# ATMEGA328P_BASICO.net
KiCad netlist of a schematic drawn in EAGLE
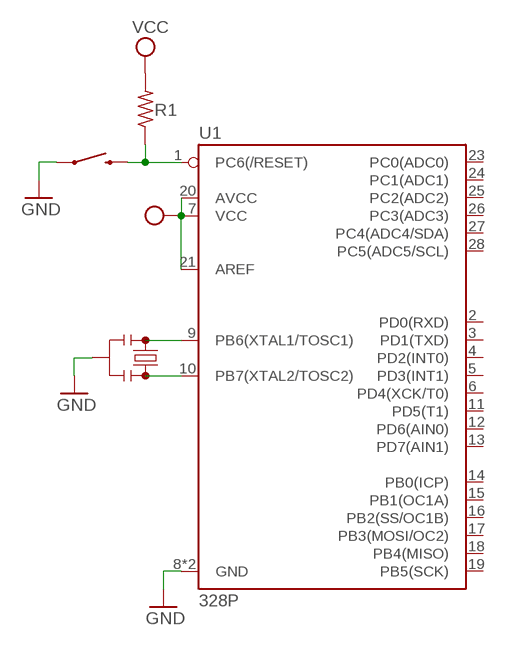
[diagram p0: schematic, sheet 1]

(export (version "E")
  (design (tool "Eeschema 10.0.6"))
  (components
    (comp (ref "R1")
      (value "R-US_0204/7")
      (footprint "eagle-import:0204_7")
      (libsource (lib "eagle-import") (part "R-US_0204/7"))
    )
    (comp (ref "S1")
      (value "MOMENTARY-SWITCH-SPST-SMD-6.2MM-TALL")
      (footprint "eagle-import:TACTILE_SWITCH_SMD_6.2MM_TALL")
      (libsource (lib "eagle-import") (part "MOMENTARY-SWITCH-SPST-SMD-6.2MM-TALL"))
    )
    (comp (ref "U1")
      (value "328P")
      (footprint "eagle-import:DIP28")
      (libsource (lib "eagle-import") (part "ATMEGA328P_PDIP"))
    )
    (comp (ref "Y1")
      (value "16MHz")
      (footprint "eagle-import:RESONATOR-SMD-3.2X1.3")
      (libsource (lib "eagle-import") (part "RESONATOR-16MHZSMD_3.2X1.3"))
    )
  )
  (nets
    (net (code "1") (name "GND") (class "Default")
      (node (ref "S1") (pin "A2") (pinfunction "1_A2") (pintype "passive"))
      (node (ref "U1") (pin "22") (pinfunction "GND_22") (pintype "bidirectional"))
      (node (ref "U1") (pin "8") (pinfunction "GND_8") (pintype "bidirectional"))
      (node (ref "Y1") (pin "2") (pinfunction "2_2") (pintype "passive"))
    )
    (net (code "2") (name "Net-(S1-2)") (class "Default")
      (node (ref "R1") (pin "1") (pinfunction "1_1") (pintype "passive"))
      (node (ref "S1") (pin "B2") (pinfunction "2_B2") (pintype "passive"))
      (node (ref "U1") (pin "1") (pinfunction "PC6(/RESET)_1") (pintype "bidirectional"))
    )
    (net (code "3") (name "Net-(U1-PB6(XTAL1{slash}TOSC1))") (class "Default")
      (node (ref "U1") (pin "9") (pinfunction "PB6(XTAL1/TOSC1)_9") (pintype "bidirectional"))
      (node (ref "Y1") (pin "1") (pinfunction "1_1") (pintype "passive"))
    )
    (net (code "4") (name "Net-(U1-PB7(XTAL2{slash}TOSC2))") (class "Default")
      (node (ref "U1") (pin "10") (pinfunction "PB7(XTAL2/TOSC2)_10") (pintype "bidirectional"))
      (node (ref "Y1") (pin "3") (pinfunction "3_3") (pintype "passive"))
    )
    (net (code "5") (name "VCC") (class "Default")
      (node (ref "R1") (pin "2") (pinfunction "2_2") (pintype "passive"))
      (node (ref "U1") (pin "20") (pinfunction "AVCC_20") (pintype "bidirectional"))
      (node (ref "U1") (pin "21") (pinfunction "AREF_21") (pintype "bidirectional"))
      (node (ref "U1") (pin "7") (pinfunction "VCC_7") (pintype "bidirectional"))
    )
    (net (code "6") (name "unconnected-(U1-PB0(ICP)-Pad14)") (class "Default")
      (node (ref "U1") (pin "14") (pinfunction "PB0(ICP)_14") (pintype "bidirectional"))
    )
    (net (code "7") (name "unconnected-(U1-PB1(OC1A)-Pad15)") (class "Default")
      (node (ref "U1") (pin "15") (pinfunction "PB1(OC1A)_15") (pintype "bidirectional"))
    )
    (net (code "8") (name "unconnected-(U1-PB2(SS{slash}OC1B)-Pad16)") (class "Default")
      (node (ref "U1") (pin "16") (pinfunction "PB2(SS/OC1B)_16") (pintype "bidirectional"))
    )
    (net (code "9") (name "unconnected-(U1-PB3(MOSI{slash}OC2)-Pad17)") (class "Default")
      (node (ref "U1") (pin "17") (pinfunction "PB3(MOSI/OC2)_17") (pintype "bidirectional"))
    )
    (net (code "10") (name "unconnected-(U1-PB4(MISO)-Pad18)") (class "Default")
      (node (ref "U1") (pin "18") (pinfunction "PB4(MISO)_18") (pintype "bidirectional"))
    )
    (net (code "11") (name "unconnected-(U1-PB5(SCK)-Pad19)") (class "Default")
      (node (ref "U1") (pin "19") (pinfunction "PB5(SCK)_19") (pintype "bidirectional"))
    )
    (net (code "12") (name "unconnected-(U1-PC0(ADC0)-Pad23)") (class "Default")
      (node (ref "U1") (pin "23") (pinfunction "PC0(ADC0)_23") (pintype "bidirectional"))
    )
    (net (code "13") (name "unconnected-(U1-PC1(ADC1)-Pad24)") (class "Default")
      (node (ref "U1") (pin "24") (pinfunction "PC1(ADC1)_24") (pintype "bidirectional"))
    )
    (net (code "14") (name "unconnected-(U1-PC2(ADC2)-Pad25)") (class "Default")
      (node (ref "U1") (pin "25") (pinfunction "PC2(ADC2)_25") (pintype "bidirectional"))
    )
    (net (code "15") (name "unconnected-(U1-PC3(ADC3)-Pad26)") (class "Default")
      (node (ref "U1") (pin "26") (pinfunction "PC3(ADC3)_26") (pintype "bidirectional"))
    )
    (net (code "16") (name "unconnected-(U1-PC4(ADC4{slash}SDA)-Pad27)") (class "Default")
      (node (ref "U1") (pin "27") (pinfunction "PC4(ADC4/SDA)_27") (pintype "bidirectional"))
    )
    (net (code "17") (name "unconnected-(U1-PC5(ADC5{slash}SCL)-Pad28)") (class "Default")
      (node (ref "U1") (pin "28") (pinfunction "PC5(ADC5/SCL)_28") (pintype "bidirectional"))
    )
    (net (code "18") (name "unconnected-(U1-PD0(RXD)-Pad2)") (class "Default")
      (node (ref "U1") (pin "2") (pinfunction "PD0(RXD)_2") (pintype "bidirectional"))
    )
    (net (code "19") (name "unconnected-(U1-PD1(TXD)-Pad3)") (class "Default")
      (node (ref "U1") (pin "3") (pinfunction "PD1(TXD)_3") (pintype "bidirectional"))
    )
    (net (code "20") (name "unconnected-(U1-PD2(INT0)-Pad4)") (class "Default")
      (node (ref "U1") (pin "4") (pinfunction "PD2(INT0)_4") (pintype "bidirectional"))
    )
    (net (code "21") (name "unconnected-(U1-PD3(INT1)-Pad5)") (class "Default")
      (node (ref "U1") (pin "5") (pinfunction "PD3(INT1)_5") (pintype "bidirectional"))
    )
    (net (code "22") (name "unconnected-(U1-PD4(XCK{slash}T0)-Pad6)") (class "Default")
      (node (ref "U1") (pin "6") (pinfunction "PD4(XCK/T0)_6") (pintype "bidirectional"))
    )
    (net (code "23") (name "unconnected-(U1-PD5(T1)-Pad11)") (class "Default")
      (node (ref "U1") (pin "11") (pinfunction "PD5(T1)_11") (pintype "bidirectional"))
    )
    (net (code "24") (name "unconnected-(U1-PD6(AIN0)-Pad12)") (class "Default")
      (node (ref "U1") (pin "12") (pinfunction "PD6(AIN0)_12") (pintype "bidirectional"))
    )
    (net (code "25") (name "unconnected-(U1-PD7(AIN1)-Pad13)") (class "Default")
      (node (ref "U1") (pin "13") (pinfunction "PD7(AIN1)_13") (pintype "bidirectional"))
    )
  )
)
